# Raspberry_Pi_3_A.net
KiCad netlist of a schematic drawn in Altium Designer
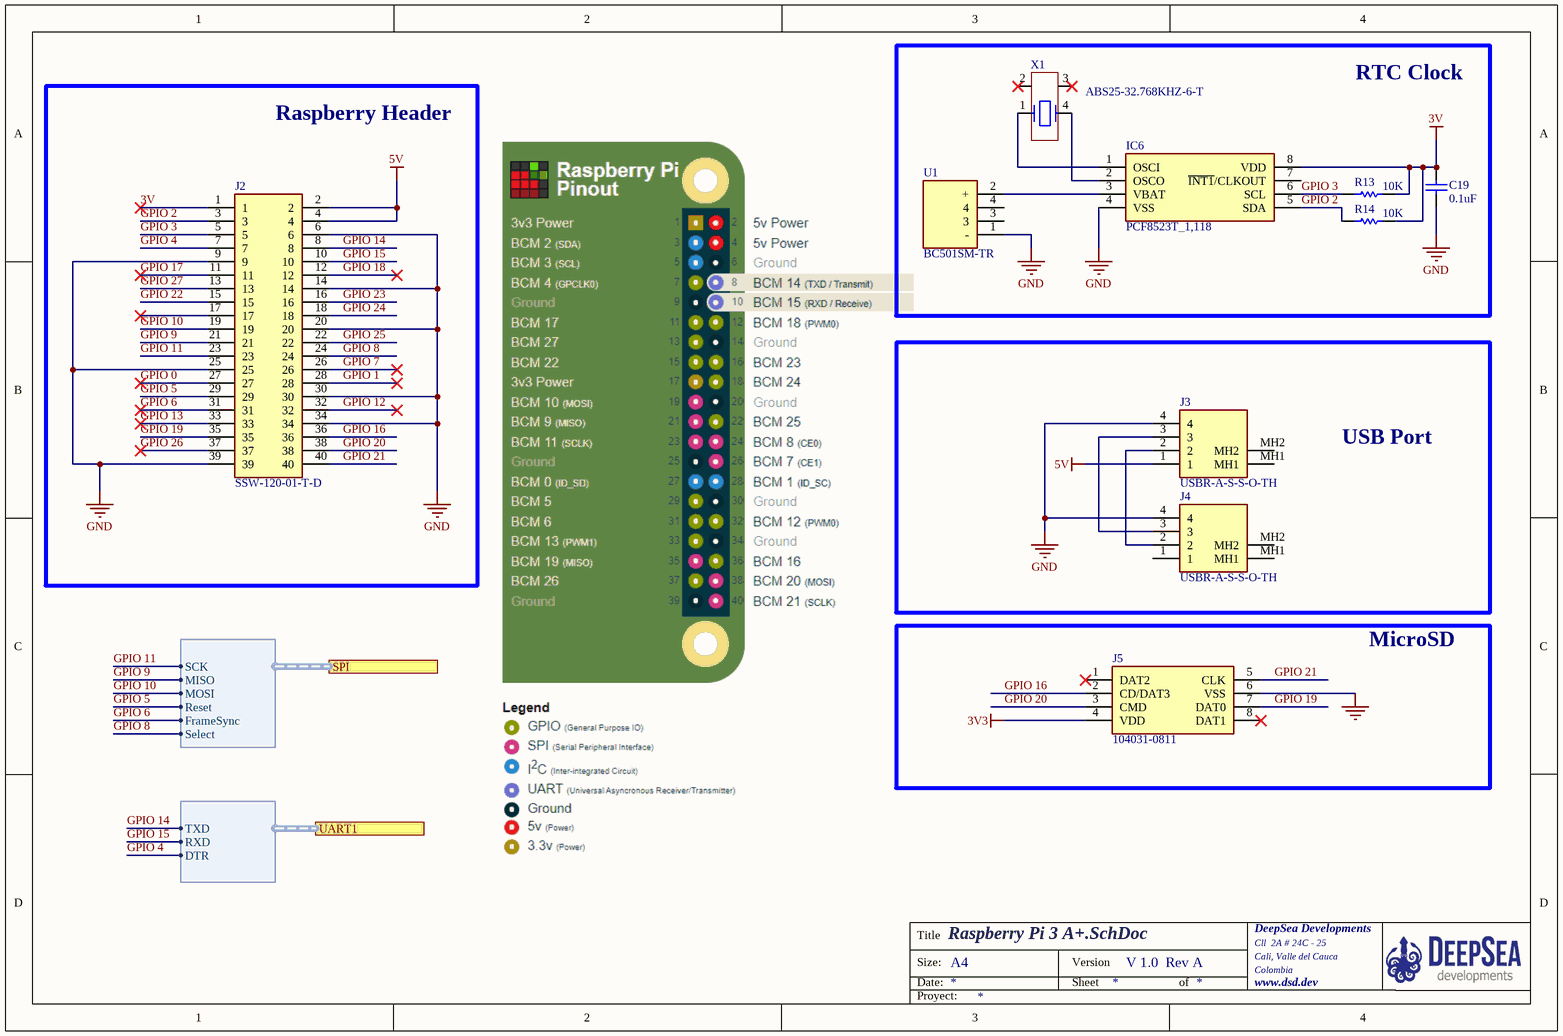
[diagram p0: Raspberry Pi 3 A+.SchDoc]

(export (version "E")
  (design (tool "Eeschema 10.0.6"))
  (components
    (comp (ref "C19") (value "0.1uF") (footprint "C0603_L") (libsource (lib "General") (part "C_SMD")))
    (comp (ref "IC6")
      (value "PCF8523T_1,118")
      (footprint "SamacSys:SOIC127P600X175-8N")
      (description "Integrated Circuit")
      (fields
        (field (name "MANUFACTURER_PART_NUMBER") "PCF8523T/1,118")
        (field (name "MOUSER PART NUMBER") "771-PCF8523T/1118")
      )
      (libsource (lib "*") (part "PCF8523T_1,118"))
    )
    (comp (ref "J2")
      (value "SSW-120-01-T-D")
      (footprint "SamacSys:RHDR40W79P254_2X20_5131X495X851P")
      (description "Connector")
      (fields (field (name "MOUSER PART NUMBER") "200-SSW12001TD") (field (name "RS PART NUMBER") "1800457"))
      (libsource (lib "SamacSys") (part "SSW-120-01-T-D"))
    )
    (comp (ref "J3")
      (value "USBR-A-S-S-O-TH")
      (footprint "SamacSys:USB_A")
      (description "Connector")
      (fields (field (name "MOUSER PART NUMBER") "200-USBRASSOTH") (field (name "RS PART NUMBER") "1800517"))
      (libsource (lib "SamacSys") (part "USBR-A-S-S-O-TH"))
    )
    (comp (ref "J4")
      (value "USBR-A-S-S-O-TH")
      (footprint "SamacSys:USB_A")
      (description "Connector")
      (fields (field (name "MOUSER PART NUMBER") "200-USBRASSOTH") (field (name "RS PART NUMBER") "1800517"))
      (libsource (lib "SamacSys") (part "USBR-A-S-S-O-TH"))
    )
    (comp (ref "J5")
      (value "104031-0811")
      (footprint "SamacSys:1040310811")
      (description "Connector")
      (fields (field (name "MOUSER PART NUMBER") "538-104031-0811") (field (name "RS PART NUMBER") "8967560"))
      (libsource (lib "*") (part "104031-0811"))
    )
    (comp (ref "R13") (value "10K") (footprint "R0603_L") (libsource (lib "General") (part "R_SMD")))
    (comp (ref "R14") (value "10K") (footprint "R0603_L") (libsource (lib "General") (part "R_SMD")))
    (comp (ref "U1")
      (value "BC501SM-TR")
      (footprint "SamacSys:BC501SMTR")
      (description "Undefined or Miscellaneous")
      (libsource (lib "*") (part "BC501SM-TR"))
    )
    (comp (ref "X1") (value "ABS25-32.768KHZ-6-T") (footprint "ABS25") (libsource (lib "*") (part "MC306")))
  )
  (nets
    (net (code "3") (name "/GPIO 0") (class "Default")
      (node (ref "J2") (pin "27") (pinfunction "27_27") (pintype "passive+no_connect"))
    )
    (net (code "4") (name "/GPIO 1") (class "Default")
      (node (ref "J2") (pin "28") (pinfunction "28_28") (pintype "passive+no_connect"))
    )
    (net (code "5") (name "/GPIO 2") (class "Default")
      (node (ref "IC6") (pin "5") (pinfunction "SDA_5") (pintype "passive"))
      (node (ref "J2") (pin "3") (pinfunction "3_3") (pintype "passive"))
      (node (ref "R14") (pin "1") (pinfunction "1_1") (pintype "passive"))
    )
    (net (code "6") (name "/GPIO 3") (class "Default")
      (node (ref "IC6") (pin "6") (pinfunction "SCL_6") (pintype "passive"))
      (node (ref "J2") (pin "5") (pinfunction "5_5") (pintype "passive"))
      (node (ref "R13") (pin "1") (pinfunction "1_1") (pintype "passive"))
    )
    (net (code "7") (name "/GPIO 4") (class "Default")
      (node (ref "J2") (pin "7") (pinfunction "7_7") (pintype "passive"))
    )
    (net (code "8") (name "/GPIO 5") (class "Default")
      (node (ref "J2") (pin "29") (pinfunction "29_29") (pintype "passive"))
    )
    (net (code "9") (name "/GPIO 6") (class "Default")
      (node (ref "J2") (pin "31") (pinfunction "31_31") (pintype "passive+no_connect"))
    )
    (net (code "10") (name "/GPIO 7") (class "Default")
      (node (ref "J2") (pin "26") (pinfunction "26_26") (pintype "passive+no_connect"))
    )
    (net (code "11") (name "/GPIO 8") (class "Default")
      (node (ref "J2") (pin "24") (pinfunction "24_24") (pintype "passive"))
    )
    (net (code "12") (name "/GPIO 9") (class "Default")
      (node (ref "J2") (pin "21") (pinfunction "21_21") (pintype "passive"))
    )
    (net (code "13") (name "/GPIO 10") (class "Default")
      (node (ref "J2") (pin "19") (pinfunction "19_19") (pintype "passive"))
    )
    (net (code "14") (name "/GPIO 11") (class "Default")
      (node (ref "J2") (pin "23") (pinfunction "23_23") (pintype "passive"))
    )
    (net (code "15") (name "/GPIO 12") (class "Default")
      (node (ref "J2") (pin "32") (pinfunction "32_32") (pintype "passive+no_connect"))
    )
    (net (code "16") (name "/GPIO 13") (class "Default")
      (node (ref "J2") (pin "33") (pinfunction "33_33") (pintype "passive+no_connect"))
    )
    (net (code "17") (name "/GPIO 14") (class "Default")
      (node (ref "J2") (pin "8") (pinfunction "8_8") (pintype "passive"))
    )
    (net (code "18") (name "/GPIO 15") (class "Default")
      (node (ref "J2") (pin "10") (pinfunction "10_10") (pintype "passive"))
    )
    (net (code "19") (name "/GPIO 16") (class "Default")
      (node (ref "J2") (pin "36") (pinfunction "36_36") (pintype "passive"))
      (node (ref "J5") (pin "2") (pinfunction "CD/DAT3_2") (pintype "passive"))
    )
    (net (code "20") (name "/GPIO 17") (class "Default")
      (node (ref "J2") (pin "11") (pinfunction "11_11") (pintype "passive+no_connect"))
    )
    (net (code "21") (name "/GPIO 18") (class "Default")
      (node (ref "J2") (pin "12") (pinfunction "12_12") (pintype "passive+no_connect"))
    )
    (net (code "22") (name "/GPIO 19") (class "Default")
      (node (ref "J2") (pin "35") (pinfunction "35_35") (pintype "passive"))
      (node (ref "J5") (pin "7") (pinfunction "DAT0_7") (pintype "passive"))
    )
    (net (code "23") (name "/GPIO 20") (class "Default")
      (node (ref "J2") (pin "38") (pinfunction "38_38") (pintype "passive"))
      (node (ref "J5") (pin "3") (pinfunction "CMD_3") (pintype "passive"))
    )
    (net (code "24") (name "/GPIO 21") (class "Default")
      (node (ref "J2") (pin "40") (pinfunction "40_40") (pintype "passive"))
      (node (ref "J5") (pin "5") (pinfunction "CLK_5") (pintype "passive"))
    )
    (net (code "25") (name "/GPIO 22") (class "Default")
      (node (ref "J2") (pin "15") (pinfunction "15_15") (pintype "passive"))
    )
    (net (code "26") (name "/GPIO 23") (class "Default")
      (node (ref "J2") (pin "16") (pinfunction "16_16") (pintype "passive"))
    )
    (net (code "27") (name "/GPIO 24") (class "Default")
      (node (ref "J2") (pin "18") (pinfunction "18_18") (pintype "passive"))
    )
    (net (code "28") (name "/GPIO 25") (class "Default")
      (node (ref "J2") (pin "22") (pinfunction "22_22") (pintype "passive"))
    )
    (net (code "29") (name "/GPIO 26") (class "Default")
      (node (ref "J2") (pin "37") (pinfunction "37_37") (pintype "passive+no_connect"))
    )
    (net (code "30") (name "/GPIO 27") (class "Default")
      (node (ref "J2") (pin "13") (pinfunction "13_13") (pintype "passive"))
    )
    (net (code "33") (name "3V") (class "Default")
      (node (ref "C19") (pin "2") (pinfunction "2_2") (pintype "passive"))
      (node (ref "IC6") (pin "8") (pinfunction "VDD_8") (pintype "passive"))
      (node (ref "J2") (pin "1") (pinfunction "1_1") (pintype "passive"))
      (node (ref "R13") (pin "2") (pinfunction "2_2") (pintype "passive"))
      (node (ref "R14") (pin "2") (pinfunction "2_2") (pintype "passive"))
    )
    (net (code "34") (name "3V3") (class "Default")
      (node (ref "J5") (pin "4") (pinfunction "VDD_4") (pintype "passive"))
    )
    (net (code "35") (name "5V") (class "Default")
      (node (ref "J2") (pin "2") (pinfunction "2_2") (pintype "passive"))
      (node (ref "J2") (pin "4") (pinfunction "4_4") (pintype "passive"))
      (node (ref "J3") (pin "1") (pinfunction "1_1") (pintype "passive"))
    )
    (net (code "36") (name "GND") (class "Default")
      (node (ref "C19") (pin "1") (pinfunction "1_1") (pintype "passive"))
      (node (ref "IC6") (pin "4") (pinfunction "VSS_4") (pintype "passive"))
      (node (ref "J2") (pin "14") (pinfunction "14_14") (pintype "passive"))
      (node (ref "J2") (pin "20") (pinfunction "20_20") (pintype "passive"))
      (node (ref "J2") (pin "25") (pinfunction "25_25") (pintype "passive"))
      (node (ref "J2") (pin "30") (pinfunction "30_30") (pintype "passive"))
      (node (ref "J2") (pin "34") (pinfunction "34_34") (pintype "passive"))
      (node (ref "J2") (pin "39") (pinfunction "39_39") (pintype "passive"))
      (node (ref "J2") (pin "6") (pinfunction "6_6") (pintype "passive"))
      (node (ref "J2") (pin "9") (pinfunction "9_9") (pintype "passive"))
      (node (ref "J3") (pin "4") (pinfunction "4_4") (pintype "passive"))
      (node (ref "J4") (pin "4") (pinfunction "4_4") (pintype "passive"))
      (node (ref "J5") (pin "6") (pinfunction "VSS_6") (pintype "passive"))
      (node (ref "U1") (pin "1") (pinfunction "-_1") (pintype "passive"))
    )
    (net (code "37") (name "Net-(IC6-OSCI)") (class "Default")
      (node (ref "IC6") (pin "1") (pinfunction "OSCI_1") (pintype "passive"))
      (node (ref "X1") (pin "1") (pinfunction "1_1") (pintype "passive"))
    )
    (net (code "38") (name "Net-(IC6-OSCO)") (class "Default")
      (node (ref "IC6") (pin "2") (pinfunction "OSCO_2") (pintype "passive"))
      (node (ref "X1") (pin "4") (pinfunction "4_4") (pintype "passive"))
    )
    (net (code "39") (name "Net-(IC6-VBAT)") (class "Default")
      (node (ref "IC6") (pin "3") (pinfunction "VBAT_3") (pintype "passive"))
      (node (ref "U1") (pin "2") (pinfunction "+_2") (pintype "passive"))
    )
    (net (code "40") (name "Net-(J3-Pad2)") (class "Default")
      (node (ref "J3") (pin "2") (pinfunction "2_2") (pintype "passive"))
      (node (ref "J4") (pin "2") (pinfunction "2_2") (pintype "passive"))
    )
    (net (code "41") (name "Net-(J3-Pad3)") (class "Default")
      (node (ref "J3") (pin "3") (pinfunction "3_3") (pintype "passive"))
      (node (ref "J4") (pin "3") (pinfunction "3_3") (pintype "passive"))
    )
    (net (code "42") (name "unconnected-(IC6-~{INT1}{slash}CLKOUT-Pad7)") (class "Default")
      (node (ref "IC6") (pin "7") (pinfunction "~{INT1}/CLKOUT_7") (pintype "passive"))
    )
    (net (code "43") (name "unconnected-(J2-Pad17)") (class "Default")
      (node (ref "J2") (pin "17") (pinfunction "17_17") (pintype "passive+no_connect"))
    )
    (net (code "44") (name "unconnected-(J3-PadMH1)") (class "Default")
      (node (ref "J3") (pin "MH1") (pinfunction "MH1_MH1") (pintype "passive"))
    )
    (net (code "45") (name "unconnected-(J3-PadMH2)") (class "Default")
      (node (ref "J3") (pin "MH2") (pinfunction "MH2_MH2") (pintype "passive"))
    )
    (net (code "46") (name "unconnected-(J4-Pad1)") (class "Default")
      (node (ref "J4") (pin "1") (pinfunction "1_1") (pintype "passive"))
    )
    (net (code "47") (name "unconnected-(J4-PadMH1)") (class "Default")
      (node (ref "J4") (pin "MH1") (pinfunction "MH1_MH1") (pintype "passive"))
    )
    (net (code "48") (name "unconnected-(J4-PadMH2)") (class "Default")
      (node (ref "J4") (pin "MH2") (pinfunction "MH2_MH2") (pintype "passive"))
    )
    (net (code "49") (name "unconnected-(J5-DAT1-Pad8)") (class "Default")
      (node (ref "J5") (pin "8") (pinfunction "DAT1_8") (pintype "passive+no_connect"))
    )
    (net (code "50") (name "unconnected-(J5-DAT2-Pad1)") (class "Default")
      (node (ref "J5") (pin "1") (pinfunction "DAT2_1") (pintype "passive+no_connect"))
    )
    (net (code "51") (name "unconnected-(U1-Pad3)") (class "Default")
      (node (ref "U1") (pin "3") (pinfunction "3_3") (pintype "passive"))
    )
    (net (code "52") (name "unconnected-(U1-Pad4)") (class "Default")
      (node (ref "U1") (pin "4") (pinfunction "4_4") (pintype "passive"))
    )
    (net (code "53") (name "unconnected-(X1-Pad2)") (class "Default")
      (node (ref "X1") (pin "2") (pinfunction "2_2") (pintype "passive+no_connect"))
    )
    (net (code "54") (name "unconnected-(X1-Pad3)") (class "Default")
      (node (ref "X1") (pin "3") (pinfunction "3_3") (pintype "passive+no_connect"))
    )
  )
)
